# -YSOLAR_PANEL_for_open_source.net
KiCad netlist of a schematic drawn in EAGLE
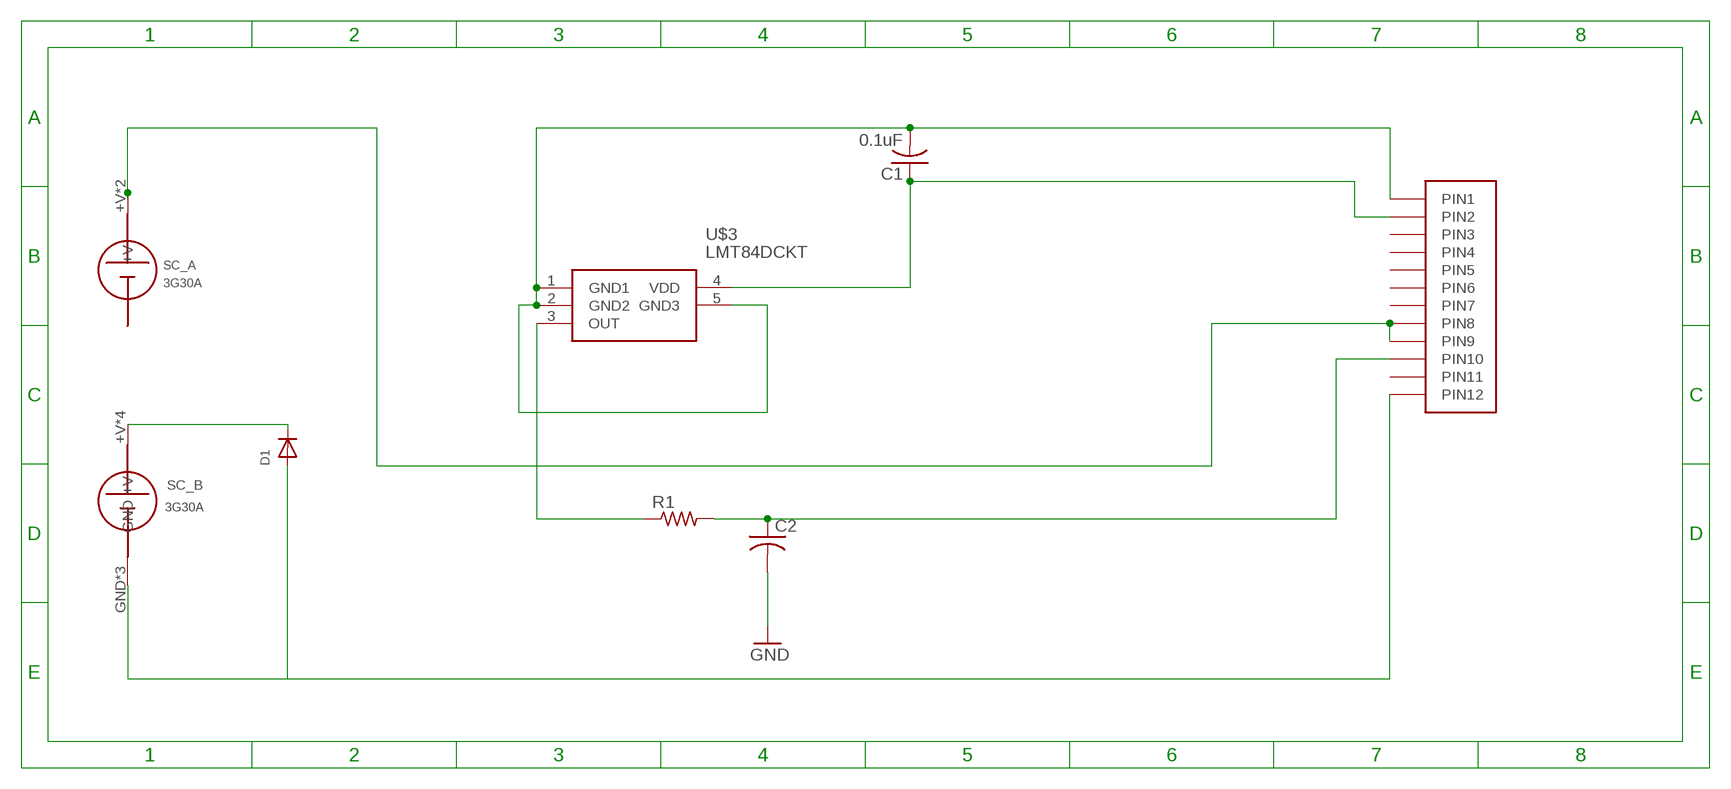
[diagram p0: schematic, sheet 1]

(export (version "E")
  (design (tool "Eeschema 10.0.6"))
  (components
    (comp (ref "C1")
      (value "0.1uF")
      (footprint "eagle-import:C0805")
      (libsource (lib "eagle-import") (part "C-USC0805"))
    )
    (comp (ref "C2")
      (value "C-USC0805")
      (footprint "eagle-import:C0805")
      (libsource (lib "eagle-import") (part "C-USC0805"))
    )
    (comp (ref "D1")
      (value "DIODE_SOD-123FL")
      (footprint "eagle-import:SOD-123FL")
      (libsource (lib "eagle-import") (part "DIODE_SOD-123FL"))
    )
    (comp (ref "R1")
      (value "R-US_R0402")
      (footprint "eagle-import:R0402")
      (libsource (lib "eagle-import") (part "R-US_R0402"))
    )
    (comp (ref "SOLARCELL_A")
      (value "SC_A")
      (footprint "eagle-import:SC_A")
      (libsource (lib "eagle-import") (part "SC_A"))
    )
    (comp (ref "SOLARCELL_B")
      (value "SC_B")
      (footprint "eagle-import:SC_B")
      (libsource (lib "eagle-import") (part "SC_B"))
    )
    (comp (ref "U$1")
      (value "HEADER12PIN")
      (footprint "eagle-import:HEADER12PIN")
      (libsource (lib "eagle-import") (part "HEADER12PIN"))
    )
    (comp (ref "U$3")
      (value "LMT84DCKT")
      (footprint "eagle-import:SOT65P210X110-5N")
      (fields (field (name "RS_PART_NUMBER") "8115860"))
      (libsource (lib "eagle-import") (part "LMT84DCKT"))
    )
  )
  (nets
    (net (code "1") (name "GND") (class "Default")
      (node (ref "C1") (pin "2") (pinfunction "2_2") (pintype "passive"))
      (node (ref "C2") (pin "2") (pinfunction "2_2") (pintype "passive"))
      (node (ref "D1") (pin "A") (pinfunction "A_A") (pintype "passive"))
      (node (ref "SOLARCELL_B") (pin "GND") (pinfunction "GND_GND") (pintype "bidirectional"))
      (node (ref "SOLARCELL_B") (pin "GND1") (pinfunction "GND_GND1") (pintype "bidirectional"))
      (node (ref "SOLARCELL_B") (pin "GND2") (pinfunction "GND_GND2") (pintype "bidirectional"))
      (node (ref "U$1") (pin "P1") (pinfunction "PIN1_P1") (pintype "bidirectional"))
      (node (ref "U$1") (pin "P12") (pinfunction "PIN12_P12") (pintype "bidirectional"))
      (node (ref "U$3") (pin "1") (pinfunction "GND1_1") (pintype "power_in"))
      (node (ref "U$3") (pin "2") (pinfunction "GND2_2") (pintype "power_in"))
      (node (ref "U$3") (pin "5") (pinfunction "GND3_5") (pintype "power_in"))
    )
    (net (code "2") (name "Net-(D1-PadC)") (class "Default")
      (node (ref "D1") (pin "C") (pinfunction "C_C") (pintype "passive"))
      (node (ref "SOLARCELL_B") (pin "+V") (pinfunction "+V_+V") (pintype "bidirectional"))
      (node (ref "SOLARCELL_B") (pin "+V2") (pinfunction "+V_+V2") (pintype "bidirectional"))
      (node (ref "SOLARCELL_B") (pin "+V3") (pinfunction "+V_+V3") (pintype "bidirectional"))
      (node (ref "SOLARCELL_B") (pin "+V4") (pinfunction "+V_+V4") (pintype "bidirectional"))
    )
    (net (code "3") (name "Net-(U$1-PIN2)") (class "Default")
      (node (ref "C1") (pin "1") (pinfunction "1_1") (pintype "passive"))
      (node (ref "U$1") (pin "P2") (pinfunction "PIN2_P2") (pintype "bidirectional"))
      (node (ref "U$3") (pin "4") (pinfunction "VDD_4") (pintype "power_in"))
    )
    (net (code "4") (name "Net-(U$1-PIN8)") (class "Default")
      (node (ref "SOLARCELL_A") (pin "+V") (pinfunction "+V_+V") (pintype "bidirectional"))
      (node (ref "SOLARCELL_A") (pin "+V1") (pinfunction "+V_+V1") (pintype "bidirectional"))
      (node (ref "U$1") (pin "P8") (pinfunction "PIN8_P8") (pintype "bidirectional"))
      (node (ref "U$1") (pin "P9") (pinfunction "PIN9_P9") (pintype "bidirectional"))
    )
    (net (code "5") (name "Net-(U$1-PIN10)") (class "Default")
      (node (ref "C2") (pin "1") (pinfunction "1_1") (pintype "passive"))
      (node (ref "R1") (pin "2") (pinfunction "2_2") (pintype "passive"))
      (node (ref "U$1") (pin "P10") (pinfunction "PIN10_P10") (pintype "bidirectional"))
    )
    (net (code "6") (name "Net-(U$3-OUT)") (class "Default")
      (node (ref "R1") (pin "1") (pinfunction "1_1") (pintype "passive"))
      (node (ref "U$3") (pin "3") (pinfunction "OUT_3") (pintype "output"))
    )
    (net (code "7") (name "unconnected-(U$1-PIN3-PadP3)") (class "Default")
      (node (ref "U$1") (pin "P3") (pinfunction "PIN3_P3") (pintype "bidirectional"))
    )
    (net (code "8") (name "unconnected-(U$1-PIN4-PadP4)") (class "Default")
      (node (ref "U$1") (pin "P4") (pinfunction "PIN4_P4") (pintype "bidirectional"))
    )
    (net (code "9") (name "unconnected-(U$1-PIN5-PadP5)") (class "Default")
      (node (ref "U$1") (pin "P5") (pinfunction "PIN5_P5") (pintype "bidirectional"))
    )
    (net (code "10") (name "unconnected-(U$1-PIN6-PadP6)") (class "Default")
      (node (ref "U$1") (pin "P6") (pinfunction "PIN6_P6") (pintype "bidirectional"))
    )
    (net (code "11") (name "unconnected-(U$1-PIN7-PadP7)") (class "Default")
      (node (ref "U$1") (pin "P7") (pinfunction "PIN7_P7") (pintype "bidirectional"))
    )
    (net (code "12") (name "unconnected-(U$1-PIN11-PadP11)") (class "Default")
      (node (ref "U$1") (pin "P11") (pinfunction "PIN11_P11") (pintype "bidirectional"))
    )
  )
)
